# PCB_Central.net
KiCad netlist of a schematic drawn in EAGLE
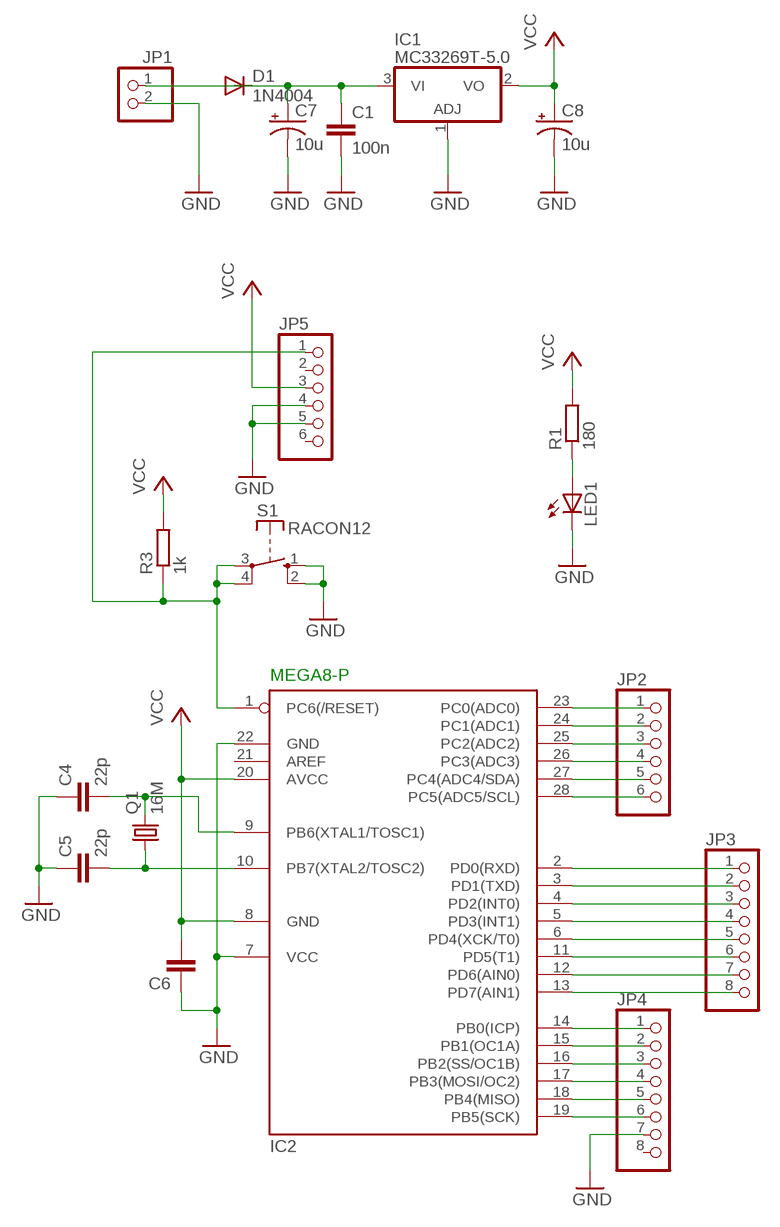
[diagram p0: schematic, sheet 1]

(export (version "E")
  (design (tool "Eeschema 10.0.6"))
  (components
    (comp (ref "C1")
      (value "100n")
      (footprint "eagle-import:C2.5-3")
      (libsource (lib "eagle-import") (part "C2,5-3"))
    )
    (comp (ref "C4")
      (value "22p")
      (footprint "eagle-import:C2.5-3")
      (libsource (lib "eagle-import") (part "C2,5-3"))
    )
    (comp (ref "C5")
      (value "22p")
      (footprint "eagle-import:C2.5-3")
      (libsource (lib "eagle-import") (part "C2,5-3"))
    )
    (comp (ref "C6")
      (value "C2,5-3")
      (footprint "eagle-import:C2.5-3")
      (libsource (lib "eagle-import") (part "C2,5-3"))
    )
    (comp (ref "C7")
      (value "10u")
      (footprint "eagle-import:E5-13")
      (libsource (lib "eagle-import") (part "CPOL-USE5-13"))
    )
    (comp (ref "C8")
      (value "10u")
      (footprint "eagle-import:E5-13")
      (libsource (lib "eagle-import") (part "CPOL-USE5-13"))
    )
    (comp (ref "D1")
      (value "1N4004")
      (footprint "eagle-import:DO41-10")
      (libsource (lib "eagle-import") (part "1N4004"))
    )
    (comp (ref "IC1")
      (value "MC33269T-5.0")
      (footprint "eagle-import:TO220V")
      (libsource (lib "eagle-import") (part "MC33269?T-5.0"))
    )
    (comp (ref "IC2")
      (value "MEGA8-P")
      (footprint "eagle-import:DIL28-3")
      (libsource (lib "eagle-import") (part "MEGA8-P"))
    )
    (comp (ref "JP1")
      (value "PINHD-1X2")
      (footprint "eagle-import:1X02")
      (libsource (lib "eagle-import") (part "PINHD-1X2"))
    )
    (comp (ref "JP2")
      (value "PINHD-1X6")
      (footprint "eagle-import:1X06")
      (libsource (lib "eagle-import") (part "PINHD-1X6"))
    )
    (comp (ref "JP3")
      (value "PINHD-1X8")
      (footprint "eagle-import:1X08")
      (libsource (lib "eagle-import") (part "PINHD-1X8"))
    )
    (comp (ref "JP4")
      (value "PINHD-1X8")
      (footprint "eagle-import:1X08")
      (libsource (lib "eagle-import") (part "PINHD-1X8"))
    )
    (comp (ref "JP5")
      (value "PINHD-1X6")
      (footprint "eagle-import:1X06")
      (libsource (lib "eagle-import") (part "PINHD-1X6"))
    )
    (comp (ref "LED1")
      (value "LED5MM")
      (footprint "eagle-import:LED5MM")
      (libsource (lib "eagle-import") (part "LED5MM"))
    )
    (comp (ref "Q1")
      (value "16M")
      (footprint "eagle-import:HC49_S")
      (libsource (lib "eagle-import") (part "CRYSTALHC49S"))
    )
    (comp (ref "R1")
      (value "180")
      (footprint "eagle-import:0207_12")
      (libsource (lib "eagle-import") (part "R-EU_0207/12"))
    )
    (comp (ref "R3")
      (value "1k")
      (footprint "eagle-import:0207_12")
      (libsource (lib "eagle-import") (part "R-EU_0207/12"))
    )
    (comp (ref "S1")
      (value "RACON12")
      (footprint "eagle-import:RACON12")
      (libsource (lib "eagle-import") (part "RACON12"))
    )
  )
  (nets
    (net (code "1") (name "GND") (class "Default")
      (node (ref "C1") (pin "2") (pinfunction "2_2") (pintype "passive"))
      (node (ref "C4") (pin "1") (pinfunction "1_1") (pintype "passive"))
      (node (ref "C5") (pin "1") (pinfunction "1_1") (pintype "passive"))
      (node (ref "C6") (pin "1") (pinfunction "1_1") (pintype "passive"))
      (node (ref "C7") (pin "-") (pinfunction "-_-") (pintype "passive"))
      (node (ref "C8") (pin "-") (pinfunction "-_-") (pintype "passive"))
      (node (ref "IC1") (pin "1") (pinfunction "ADJ_1") (pintype "input"))
      (node (ref "IC2") (pin "22") (pinfunction "GND_22") (pintype "power_in"))
      (node (ref "IC2") (pin "7") (pinfunction "VCC_7") (pintype "power_in"))
      (node (ref "JP1") (pin "2") (pinfunction "2_2") (pintype "passive"))
      (node (ref "JP4") (pin "7") (pinfunction "7_7") (pintype "passive"))
      (node (ref "JP5") (pin "4") (pinfunction "4_4") (pintype "passive"))
      (node (ref "JP5") (pin "5") (pinfunction "5_5") (pintype "passive"))
      (node (ref "LED1") (pin "K") (pinfunction "C_K") (pintype "passive"))
      (node (ref "S1") (pin "1") (pinfunction "S_1") (pintype "passive"))
      (node (ref "S1") (pin "2") (pinfunction "S_2") (pintype "passive"))
    )
    (net (code "2") (name "Net-(IC1-VI)") (class "Default")
      (node (ref "C1") (pin "1") (pinfunction "1_1") (pintype "passive"))
      (node (ref "C7") (pin "+") (pinfunction "+_+") (pintype "passive"))
      (node (ref "D1") (pin "A") (pinfunction "A_A") (pintype "passive"))
      (node (ref "D1") (pin "C") (pinfunction "C_C") (pintype "passive"))
      (node (ref "IC1") (pin "3") (pinfunction "VI_3") (pintype "input"))
      (node (ref "JP1") (pin "1") (pinfunction "1_1") (pintype "passive"))
    )
    (net (code "3") (name "Net-(IC2-PB0(ICP))") (class "Default")
      (node (ref "IC2") (pin "14") (pinfunction "PB0(ICP)_14") (pintype "bidirectional"))
      (node (ref "JP4") (pin "1") (pinfunction "1_1") (pintype "passive"))
    )
    (net (code "4") (name "Net-(IC2-PB1(OC1A))") (class "Default")
      (node (ref "IC2") (pin "15") (pinfunction "PB1(OC1A)_15") (pintype "bidirectional"))
      (node (ref "JP4") (pin "2") (pinfunction "2_2") (pintype "passive"))
    )
    (net (code "5") (name "Net-(IC2-PB2(SS{slash}OC1B))") (class "Default")
      (node (ref "IC2") (pin "16") (pinfunction "PB2(SS/OC1B)_16") (pintype "bidirectional"))
      (node (ref "JP4") (pin "3") (pinfunction "3_3") (pintype "passive"))
    )
    (net (code "6") (name "Net-(IC2-PB3(MOSI{slash}OC2))") (class "Default")
      (node (ref "IC2") (pin "17") (pinfunction "PB3(MOSI/OC2)_17") (pintype "bidirectional"))
      (node (ref "JP4") (pin "4") (pinfunction "4_4") (pintype "passive"))
    )
    (net (code "7") (name "Net-(IC2-PB4(MISO))") (class "Default")
      (node (ref "IC2") (pin "18") (pinfunction "PB4(MISO)_18") (pintype "bidirectional"))
      (node (ref "JP4") (pin "5") (pinfunction "5_5") (pintype "passive"))
    )
    (net (code "8") (name "Net-(IC2-PB5(SCK))") (class "Default")
      (node (ref "IC2") (pin "19") (pinfunction "PB5(SCK)_19") (pintype "bidirectional"))
      (node (ref "JP4") (pin "6") (pinfunction "6_6") (pintype "passive"))
    )
    (net (code "9") (name "Net-(IC2-PB6(XTAL1{slash}TOSC1))") (class "Default")
      (node (ref "C4") (pin "2") (pinfunction "2_2") (pintype "passive"))
      (node (ref "IC2") (pin "9") (pinfunction "PB6(XTAL1/TOSC1)_9") (pintype "bidirectional"))
      (node (ref "Q1") (pin "2") (pinfunction "2_2") (pintype "passive"))
    )
    (net (code "10") (name "Net-(IC2-PB7(XTAL2{slash}TOSC2))") (class "Default")
      (node (ref "C5") (pin "2") (pinfunction "2_2") (pintype "passive"))
      (node (ref "IC2") (pin "10") (pinfunction "PB7(XTAL2/TOSC2)_10") (pintype "bidirectional"))
      (node (ref "Q1") (pin "1") (pinfunction "1_1") (pintype "passive"))
    )
    (net (code "11") (name "Net-(IC2-PC0(ADC0))") (class "Default")
      (node (ref "IC2") (pin "23") (pinfunction "PC0(ADC0)_23") (pintype "bidirectional"))
      (node (ref "JP2") (pin "1") (pinfunction "1_1") (pintype "passive"))
    )
    (net (code "12") (name "Net-(IC2-PC1(ADC1))") (class "Default")
      (node (ref "IC2") (pin "24") (pinfunction "PC1(ADC1)_24") (pintype "bidirectional"))
      (node (ref "JP2") (pin "2") (pinfunction "2_2") (pintype "passive"))
    )
    (net (code "13") (name "Net-(IC2-PC2(ADC2))") (class "Default")
      (node (ref "IC2") (pin "25") (pinfunction "PC2(ADC2)_25") (pintype "bidirectional"))
      (node (ref "JP2") (pin "3") (pinfunction "3_3") (pintype "passive"))
    )
    (net (code "14") (name "Net-(IC2-PC3(ADC3))") (class "Default")
      (node (ref "IC2") (pin "26") (pinfunction "PC3(ADC3)_26") (pintype "bidirectional"))
      (node (ref "JP2") (pin "4") (pinfunction "4_4") (pintype "passive"))
    )
    (net (code "15") (name "Net-(IC2-PC4(ADC4{slash}SDA))") (class "Default")
      (node (ref "IC2") (pin "27") (pinfunction "PC4(ADC4/SDA)_27") (pintype "bidirectional"))
      (node (ref "JP2") (pin "5") (pinfunction "5_5") (pintype "passive"))
    )
    (net (code "16") (name "Net-(IC2-PC5(ADC5{slash}SCL))") (class "Default")
      (node (ref "IC2") (pin "28") (pinfunction "PC5(ADC5/SCL)_28") (pintype "bidirectional"))
      (node (ref "JP2") (pin "6") (pinfunction "6_6") (pintype "passive"))
    )
    (net (code "17") (name "Net-(IC2-PC6({slash}RESET))") (class "Default")
      (node (ref "IC2") (pin "1") (pinfunction "PC6(/RESET)_1") (pintype "bidirectional"))
      (node (ref "JP5") (pin "1") (pinfunction "1_1") (pintype "passive"))
      (node (ref "R3") (pin "1") (pinfunction "1_1") (pintype "passive"))
      (node (ref "S1") (pin "3") (pinfunction "P_3") (pintype "passive"))
      (node (ref "S1") (pin "4") (pinfunction "P_4") (pintype "passive"))
    )
    (net (code "18") (name "Net-(IC2-PD0(RXD))") (class "Default")
      (node (ref "IC2") (pin "2") (pinfunction "PD0(RXD)_2") (pintype "bidirectional"))
      (node (ref "JP3") (pin "1") (pinfunction "1_1") (pintype "passive"))
    )
    (net (code "19") (name "Net-(IC2-PD1(TXD))") (class "Default")
      (node (ref "IC2") (pin "3") (pinfunction "PD1(TXD)_3") (pintype "bidirectional"))
      (node (ref "JP3") (pin "2") (pinfunction "2_2") (pintype "passive"))
    )
    (net (code "20") (name "Net-(IC2-PD2(INT0))") (class "Default")
      (node (ref "IC2") (pin "4") (pinfunction "PD2(INT0)_4") (pintype "bidirectional"))
      (node (ref "JP3") (pin "3") (pinfunction "3_3") (pintype "passive"))
    )
    (net (code "21") (name "Net-(IC2-PD3(INT1))") (class "Default")
      (node (ref "IC2") (pin "5") (pinfunction "PD3(INT1)_5") (pintype "bidirectional"))
      (node (ref "JP3") (pin "4") (pinfunction "4_4") (pintype "passive"))
    )
    (net (code "22") (name "Net-(IC2-PD4(XCK{slash}T0))") (class "Default")
      (node (ref "IC2") (pin "6") (pinfunction "PD4(XCK/T0)_6") (pintype "bidirectional"))
      (node (ref "JP3") (pin "5") (pinfunction "5_5") (pintype "passive"))
    )
    (net (code "23") (name "Net-(IC2-PD5(T1))") (class "Default")
      (node (ref "IC2") (pin "11") (pinfunction "PD5(T1)_11") (pintype "bidirectional"))
      (node (ref "JP3") (pin "6") (pinfunction "6_6") (pintype "passive"))
    )
    (net (code "24") (name "Net-(IC2-PD6(AIN0))") (class "Default")
      (node (ref "IC2") (pin "12") (pinfunction "PD6(AIN0)_12") (pintype "bidirectional"))
      (node (ref "JP3") (pin "7") (pinfunction "7_7") (pintype "passive"))
    )
    (net (code "25") (name "Net-(IC2-PD7(AIN1))") (class "Default")
      (node (ref "IC2") (pin "13") (pinfunction "PD7(AIN1)_13") (pintype "bidirectional"))
      (node (ref "JP3") (pin "8") (pinfunction "8_8") (pintype "passive"))
    )
    (net (code "26") (name "Net-(LED1-PadA)") (class "Default")
      (node (ref "LED1") (pin "A") (pinfunction "A_A") (pintype "passive"))
      (node (ref "R1") (pin "1") (pinfunction "1_1") (pintype "passive"))
    )
    (net (code "27") (name "VCC") (class "Default")
      (node (ref "C6") (pin "2") (pinfunction "2_2") (pintype "passive"))
      (node (ref "C8") (pin "+") (pinfunction "+_+") (pintype "passive"))
      (node (ref "IC1") (pin "2") (pinfunction "VO_2") (pintype "passive"))
      (node (ref "IC2") (pin "20") (pinfunction "AVCC_20") (pintype "power_in"))
      (node (ref "IC2") (pin "8") (pinfunction "GND_8") (pintype "power_in"))
      (node (ref "JP5") (pin "3") (pinfunction "3_3") (pintype "passive"))
      (node (ref "R1") (pin "2") (pinfunction "2_2") (pintype "passive"))
      (node (ref "R3") (pin "2") (pinfunction "2_2") (pintype "passive"))
    )
    (net (code "28") (name "unconnected-(IC2-AREF-Pad21)") (class "Default")
      (node (ref "IC2") (pin "21") (pinfunction "AREF_21") (pintype "passive"))
    )
    (net (code "29") (name "unconnected-(JP4-Pad8)") (class "Default")
      (node (ref "JP4") (pin "8") (pinfunction "8_8") (pintype "passive"))
    )
    (net (code "30") (name "unconnected-(JP5-Pad2)") (class "Default")
      (node (ref "JP5") (pin "2") (pinfunction "2_2") (pintype "passive"))
    )
    (net (code "31") (name "unconnected-(JP5-Pad6)") (class "Default")
      (node (ref "JP5") (pin "6") (pinfunction "6_6") (pintype "passive"))
    )
  )
)
